# Enviroment_revision.net
KiCad netlist of a schematic drawn in EasyEDA Pro
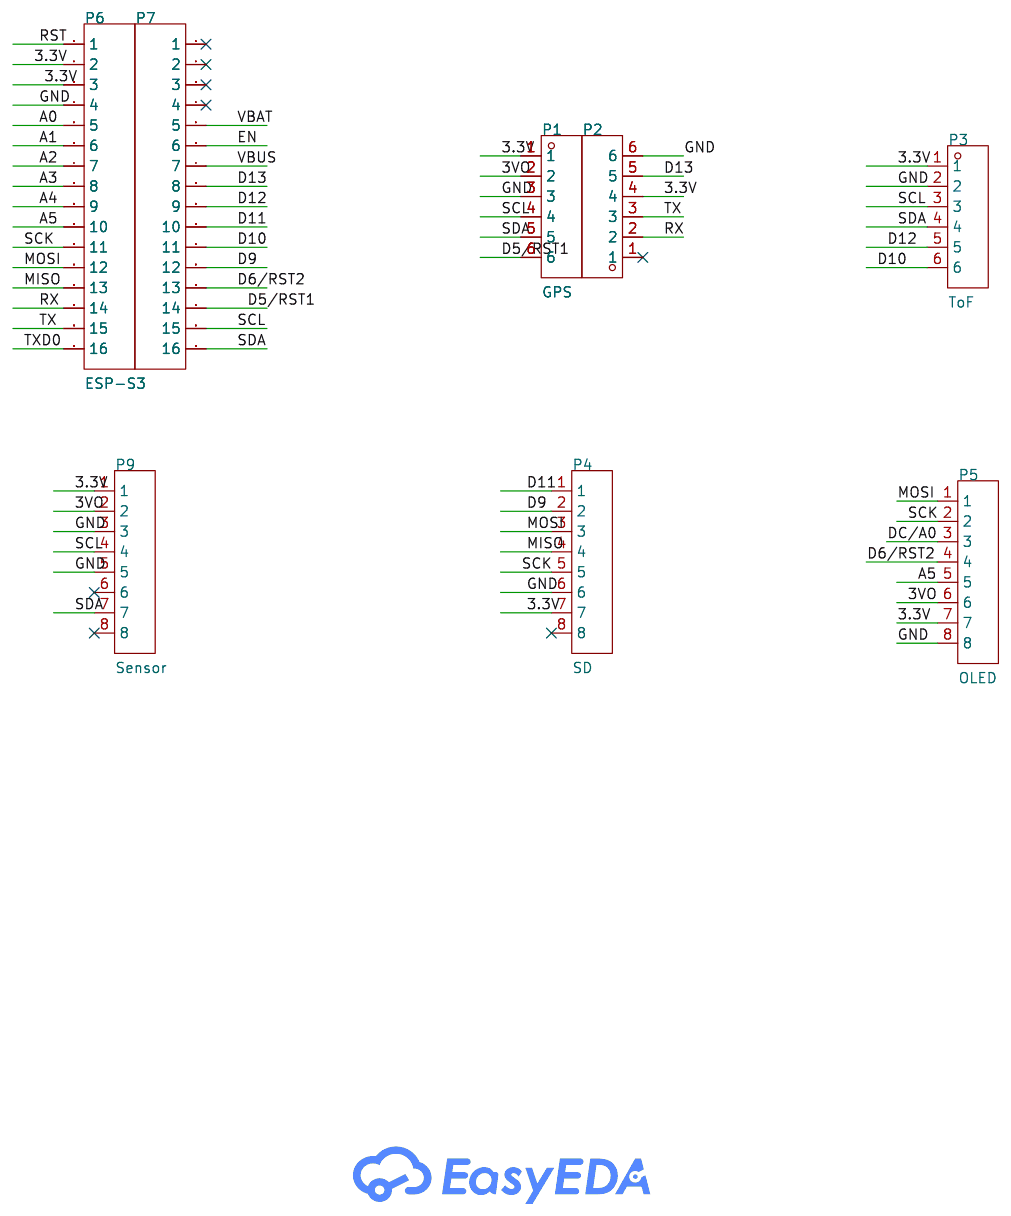
[diagram p0: schematic sheet]

(export (version "E")
  (design (tool "Eeschema 10.0.6"))
  (components
    (comp (ref "P1")
      (value "GPS")
      (footprint "easyedapro:HDR-TH_6P-P2.54-V-F")
      (fields (field (name "Manufacturer") "BOOMELE(博穆精密)"))
      (libsource (lib "easyedapro") (part "Header-Female-2.54_1x6"))
    )
    (comp (ref "P2")
      (value "2.54-1*6P母")
      (footprint "easyedapro:HDR-TH_6P-P2.54-V-F")
      (fields (field (name "Manufacturer") "BOOMELE(博穆精密)"))
      (libsource (lib "easyedapro") (part "Header-Female-2.54_1x6"))
    )
    (comp (ref "P3")
      (value "ToF")
      (footprint "easyedapro:HDR-TH_6P-P2.54-V-F")
      (fields (field (name "Manufacturer") "BOOMELE(博穆精密)"))
      (libsource (lib "easyedapro") (part "Header-Female-2.54_1x6"))
    )
    (comp (ref "P4")
      (value "SD")
      (footprint "easyedapro:HDR-TH_8P-P2.54-V-F_2")
      (fields (field (name "Manufacturer") "BOOMELE(博穆精密)"))
      (libsource (lib "easyedapro") (part "Header-Female-2.54_1x8"))
    )
    (comp (ref "P5")
      (value "OLED")
      (footprint "easyedapro:HDR-TH_8P-P2.54-V-F_2")
      (fields (field (name "Manufacturer") "BOOMELE(博穆精密)"))
      (libsource (lib "easyedapro") (part "Header-Female-2.54_1x8"))
    )
    (comp (ref "P6")
      (value "ESP-S3")
      (footprint "easyedapro:HDR-TH_16P-P2.54-V-F-1")
      (fields (field (name "Manufacturer") "BOOMELE(博穆精密)"))
      (libsource (lib "easyedapro") (part "Header-Female-2.54_1x16"))
    )
    (comp (ref "P7")
      (value "2.54-1*16P母")
      (footprint "easyedapro:HDR-TH_16P-P2.54-V-F-1")
      (fields (field (name "Manufacturer") "BOOMELE(博穆精密)"))
      (libsource (lib "easyedapro") (part "Header-Female-2.54_1x16"))
    )
    (comp (ref "P9")
      (value "Sensor")
      (footprint "easyedapro:HDR-TH_8P-P2.54-V-F_2")
      (fields (field (name "Manufacturer") "BOOMELE(博穆精密)"))
      (libsource (lib "easyedapro") (part "Header-Female-2.54_1x8"))
    )
  )
  (nets
    (net (code "1") (name "/3.3V") (class "Default")
      (node (ref "P1") (pin "1") (pinfunction "1_1") (pintype "input"))
      (node (ref "P2") (pin "4") (pinfunction "4_4") (pintype "input"))
      (node (ref "P3") (pin "1") (pinfunction "1_1") (pintype "input"))
      (node (ref "P4") (pin "7") (pinfunction "7_7") (pintype "unspecified"))
      (node (ref "P5") (pin "7") (pinfunction "7_7") (pintype "unspecified"))
      (node (ref "P6") (pin "2") (pinfunction "2_2") (pintype "input"))
      (node (ref "P6") (pin "3") (pinfunction "3_3") (pintype "input"))
      (node (ref "P9") (pin "1") (pinfunction "1_1") (pintype "unspecified"))
    )
    (net (code "2") (name "/3VO") (class "Default")
      (node (ref "P1") (pin "2") (pinfunction "2_2") (pintype "input"))
      (node (ref "P5") (pin "6") (pinfunction "6_6") (pintype "unspecified"))
      (node (ref "P9") (pin "2") (pinfunction "2_2") (pintype "unspecified"))
    )
    (net (code "3") (name "/A0") (class "Default")
      (node (ref "P6") (pin "5") (pinfunction "5_5") (pintype "input"))
    )
    (net (code "4") (name "/A1") (class "Default")
      (node (ref "P6") (pin "6") (pinfunction "6_6") (pintype "input"))
    )
    (net (code "5") (name "/A2") (class "Default")
      (node (ref "P6") (pin "7") (pinfunction "7_7") (pintype "input"))
    )
    (net (code "6") (name "/A3") (class "Default")
      (node (ref "P6") (pin "8") (pinfunction "8_8") (pintype "input"))
    )
    (net (code "7") (name "/A4") (class "Default")
      (node (ref "P6") (pin "9") (pinfunction "9_9") (pintype "input"))
    )
    (net (code "8") (name "/A5") (class "Default")
      (node (ref "P5") (pin "5") (pinfunction "5_5") (pintype "unspecified"))
      (node (ref "P6") (pin "10") (pinfunction "10_10") (pintype "input"))
    )
    (net (code "9") (name "/D5{slash}RST1") (class "Default")
      (node (ref "P1") (pin "6") (pinfunction "6_6") (pintype "input"))
      (node (ref "P7") (pin "14") (pinfunction "14_14") (pintype "input"))
    )
    (net (code "10") (name "/D6{slash}RST2") (class "Default")
      (node (ref "P5") (pin "4") (pinfunction "4_4") (pintype "unspecified"))
      (node (ref "P7") (pin "13") (pinfunction "13_13") (pintype "input"))
    )
    (net (code "11") (name "/D9") (class "Default")
      (node (ref "P4") (pin "2") (pinfunction "2_2") (pintype "unspecified"))
      (node (ref "P7") (pin "12") (pinfunction "12_12") (pintype "input"))
    )
    (net (code "12") (name "/D10") (class "Default")
      (node (ref "P3") (pin "6") (pinfunction "6_6") (pintype "input"))
      (node (ref "P7") (pin "11") (pinfunction "11_11") (pintype "input"))
    )
    (net (code "13") (name "/D11") (class "Default")
      (node (ref "P4") (pin "1") (pinfunction "1_1") (pintype "unspecified"))
      (node (ref "P7") (pin "10") (pinfunction "10_10") (pintype "input"))
    )
    (net (code "14") (name "/D12") (class "Default")
      (node (ref "P3") (pin "5") (pinfunction "5_5") (pintype "input"))
      (node (ref "P7") (pin "9") (pinfunction "9_9") (pintype "input"))
    )
    (net (code "15") (name "/D13") (class "Default")
      (node (ref "P2") (pin "5") (pinfunction "5_5") (pintype "input"))
      (node (ref "P7") (pin "8") (pinfunction "8_8") (pintype "input"))
    )
    (net (code "16") (name "/DC{slash}A0") (class "Default")
      (node (ref "P5") (pin "3") (pinfunction "3_3") (pintype "unspecified"))
    )
    (net (code "17") (name "/EN") (class "Default")
      (node (ref "P7") (pin "6") (pinfunction "6_6") (pintype "input"))
    )
    (net (code "18") (name "/GND") (class "Default")
      (node (ref "P1") (pin "3") (pinfunction "3_3") (pintype "input"))
      (node (ref "P2") (pin "6") (pinfunction "6_6") (pintype "input"))
      (node (ref "P3") (pin "2") (pinfunction "2_2") (pintype "input"))
      (node (ref "P4") (pin "6") (pinfunction "6_6") (pintype "unspecified"))
      (node (ref "P5") (pin "8") (pinfunction "8_8") (pintype "unspecified"))
      (node (ref "P6") (pin "4") (pinfunction "4_4") (pintype "input"))
      (node (ref "P9") (pin "3") (pinfunction "3_3") (pintype "unspecified"))
      (node (ref "P9") (pin "5") (pinfunction "5_5") (pintype "unspecified"))
    )
    (net (code "19") (name "/MISO") (class "Default")
      (node (ref "P4") (pin "4") (pinfunction "4_4") (pintype "unspecified"))
      (node (ref "P6") (pin "13") (pinfunction "13_13") (pintype "input"))
    )
    (net (code "20") (name "/MOSI") (class "Default")
      (node (ref "P4") (pin "3") (pinfunction "3_3") (pintype "unspecified"))
      (node (ref "P5") (pin "1") (pinfunction "1_1") (pintype "unspecified"))
      (node (ref "P6") (pin "12") (pinfunction "12_12") (pintype "input"))
    )
    (net (code "21") (name "/RST") (class "Default")
      (node (ref "P6") (pin "1") (pinfunction "1_1") (pintype "input"))
    )
    (net (code "22") (name "/RX") (class "Default")
      (node (ref "P2") (pin "2") (pinfunction "2_2") (pintype "input"))
      (node (ref "P6") (pin "14") (pinfunction "14_14") (pintype "input"))
    )
    (net (code "23") (name "/SCK") (class "Default")
      (node (ref "P4") (pin "5") (pinfunction "5_5") (pintype "unspecified"))
      (node (ref "P5") (pin "2") (pinfunction "2_2") (pintype "unspecified"))
      (node (ref "P6") (pin "11") (pinfunction "11_11") (pintype "input"))
    )
    (net (code "24") (name "/SCL") (class "Default")
      (node (ref "P1") (pin "4") (pinfunction "4_4") (pintype "input"))
      (node (ref "P3") (pin "3") (pinfunction "3_3") (pintype "input"))
      (node (ref "P7") (pin "15") (pinfunction "15_15") (pintype "input"))
      (node (ref "P9") (pin "4") (pinfunction "4_4") (pintype "unspecified"))
    )
    (net (code "25") (name "/SDA") (class "Default")
      (node (ref "P1") (pin "5") (pinfunction "5_5") (pintype "input"))
      (node (ref "P3") (pin "4") (pinfunction "4_4") (pintype "input"))
      (node (ref "P7") (pin "16") (pinfunction "16_16") (pintype "input"))
      (node (ref "P9") (pin "7") (pinfunction "7_7") (pintype "unspecified"))
    )
    (net (code "26") (name "/TX") (class "Default")
      (node (ref "P2") (pin "3") (pinfunction "3_3") (pintype "input"))
      (node (ref "P6") (pin "15") (pinfunction "15_15") (pintype "input"))
    )
    (net (code "27") (name "/TXD0") (class "Default")
      (node (ref "P6") (pin "16") (pinfunction "16_16") (pintype "input"))
    )
    (net (code "28") (name "/VBAT") (class "Default")
      (node (ref "P7") (pin "5") (pinfunction "5_5") (pintype "input"))
    )
    (net (code "29") (name "/VBUS") (class "Default")
      (node (ref "P7") (pin "7") (pinfunction "7_7") (pintype "input"))
    )
    (net (code "30") (name "unconnected-(P2-Pad1)") (class "Default")
      (node (ref "P2") (pin "1") (pinfunction "1_1") (pintype "input+no_connect"))
    )
    (net (code "31") (name "unconnected-(P4-Pad8)") (class "Default")
      (node (ref "P4") (pin "8") (pinfunction "8_8") (pintype "unspecified+no_connect"))
    )
    (net (code "32") (name "unconnected-(P7-Pad1)") (class "Default")
      (node (ref "P7") (pin "1") (pinfunction "1_1") (pintype "input+no_connect"))
    )
    (net (code "33") (name "unconnected-(P7-Pad2)") (class "Default")
      (node (ref "P7") (pin "2") (pinfunction "2_2") (pintype "input+no_connect"))
    )
    (net (code "34") (name "unconnected-(P7-Pad3)") (class "Default")
      (node (ref "P7") (pin "3") (pinfunction "3_3") (pintype "input+no_connect"))
    )
    (net (code "35") (name "unconnected-(P7-Pad4)") (class "Default")
      (node (ref "P7") (pin "4") (pinfunction "4_4") (pintype "input+no_connect"))
    )
    (net (code "36") (name "unconnected-(P9-Pad6)") (class "Default")
      (node (ref "P9") (pin "6") (pinfunction "6_6") (pintype "unspecified+no_connect"))
    )
    (net (code "37") (name "unconnected-(P9-Pad8)") (class "Default")
      (node (ref "P9") (pin "8") (pinfunction "8_8") (pintype "unspecified+no_connect"))
    )
  )
)
